# SCH_StringShotter_2025-03-04.net
KiCad netlist of a schematic drawn in EasyEDA
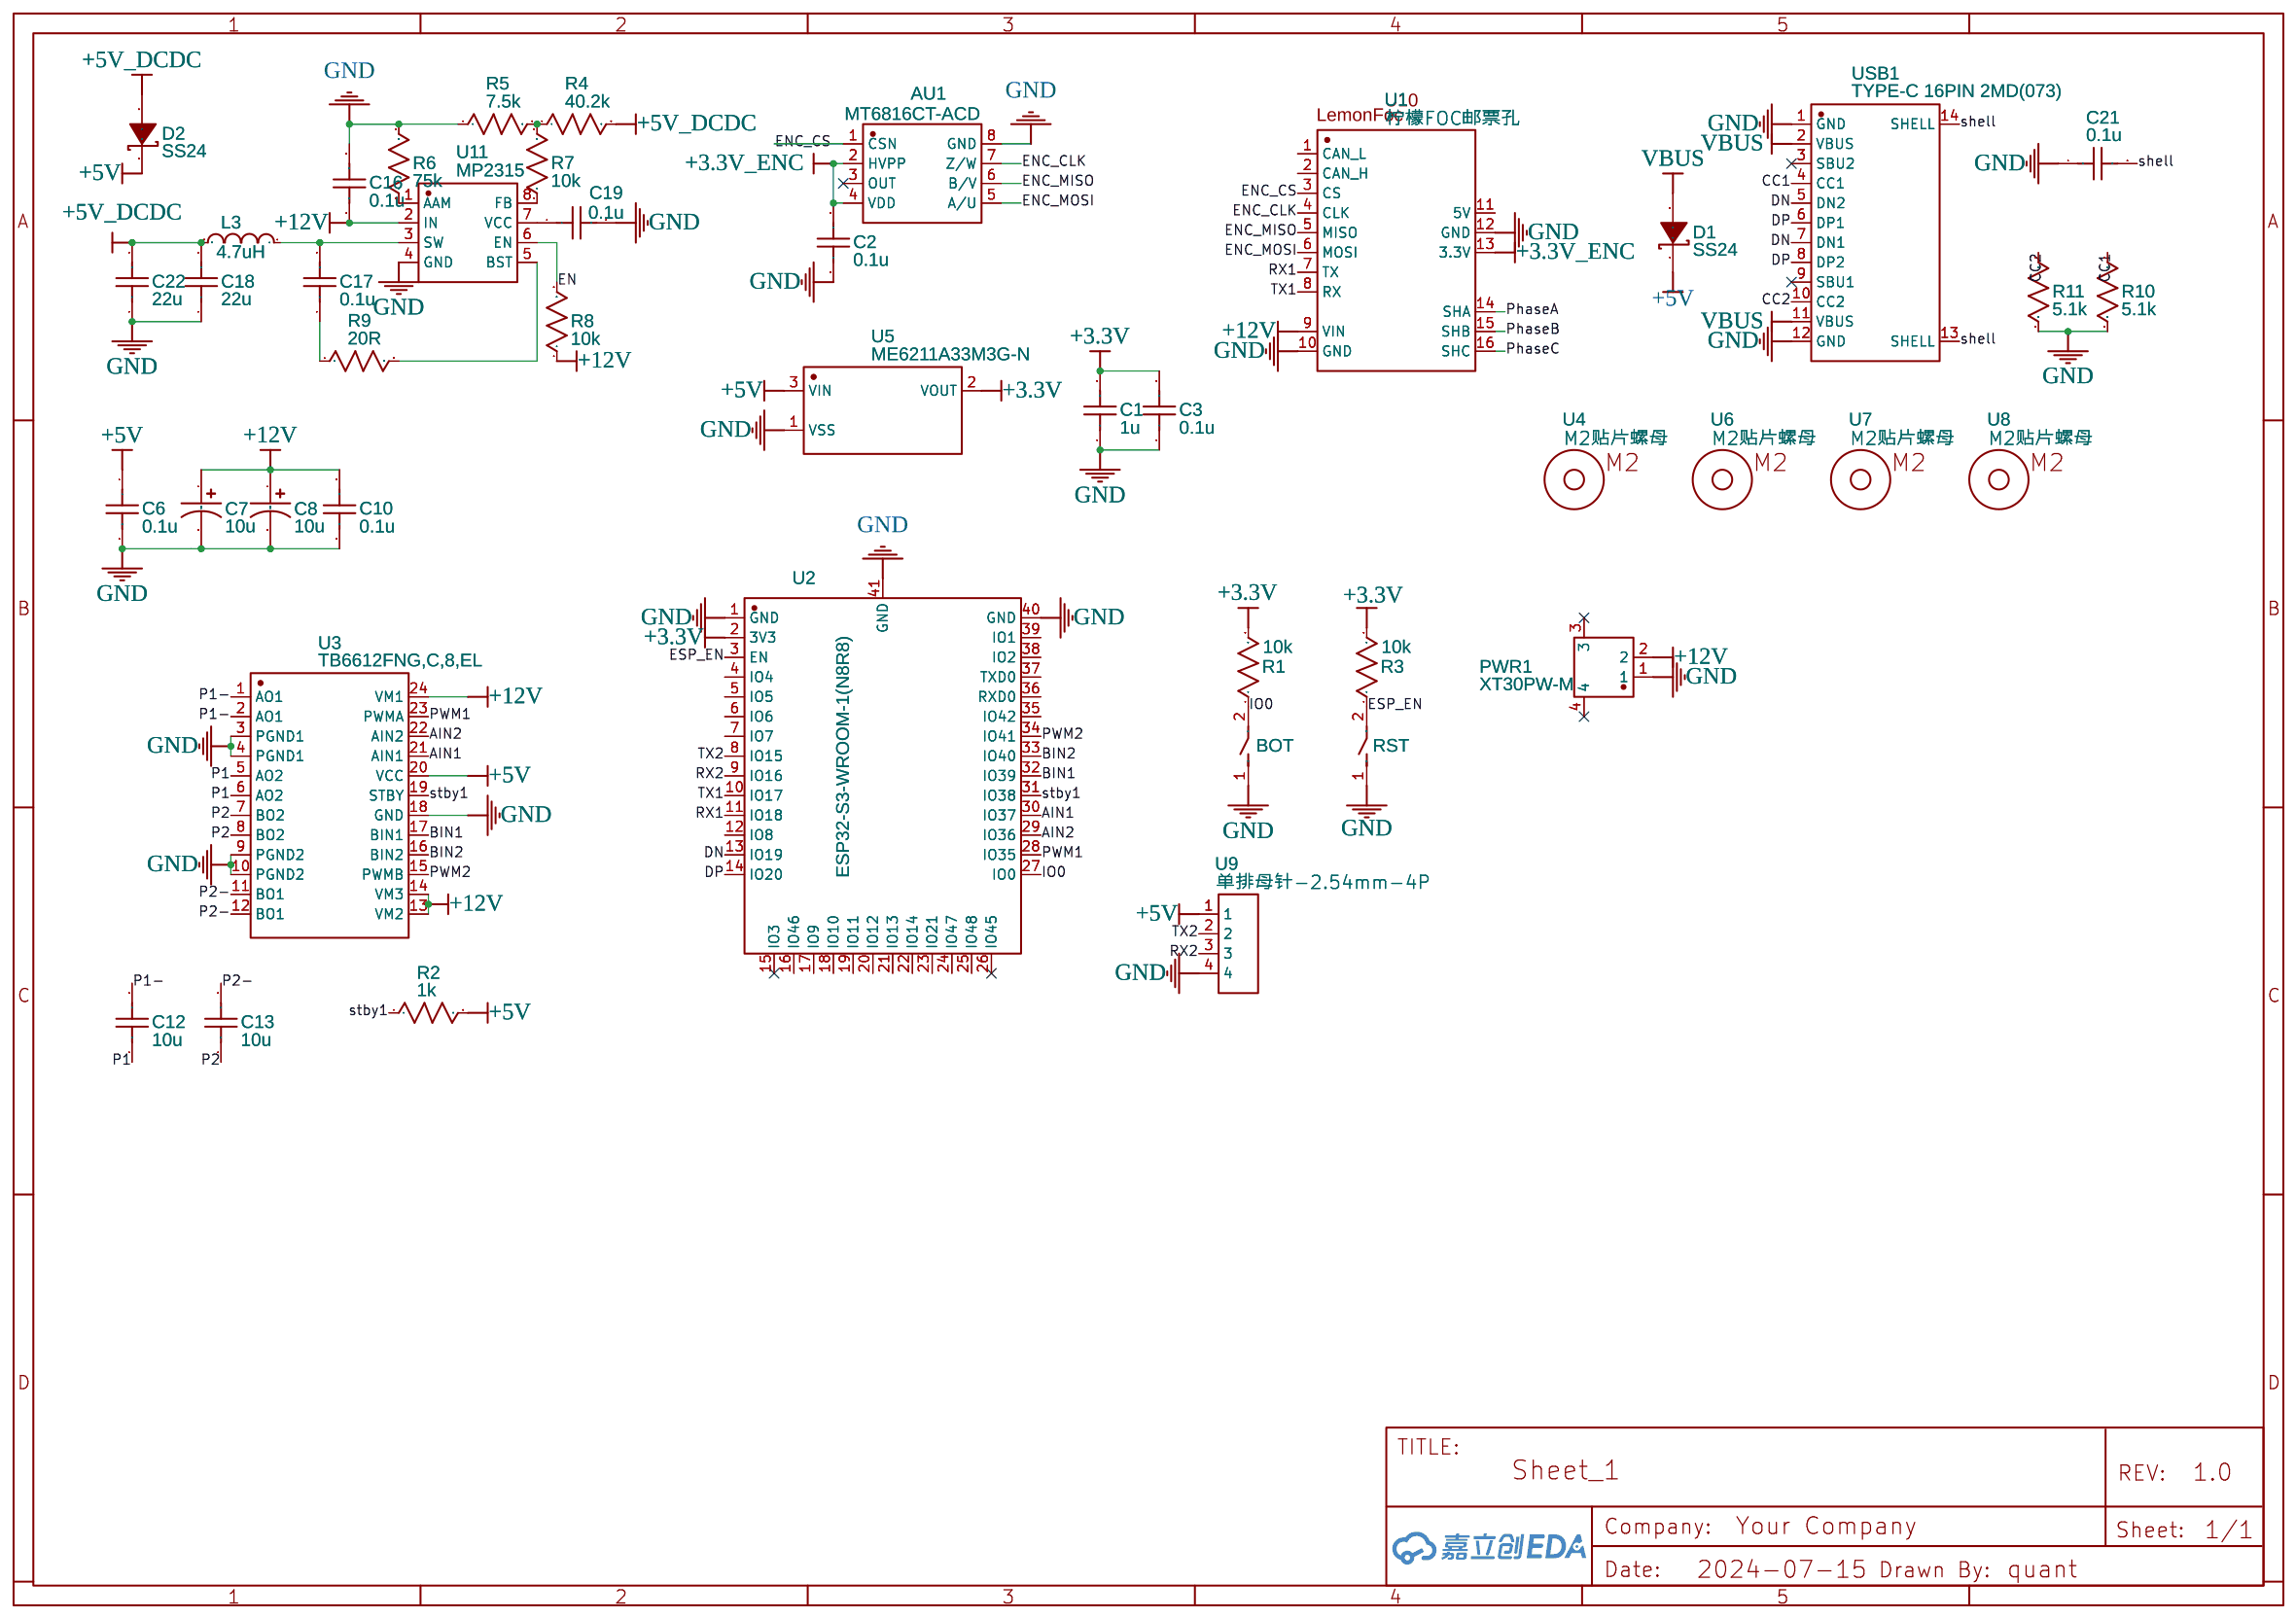
[diagram p0: schematic sheet]

(export (version "E")
  (design (tool "Eeschema 10.0.6"))
  (components
    (comp (ref "AU1")
      (value "MT6816CT-ACD")
      (fields (field (name "Manufacturer") "Magn Tek"))
      (libsource (lib "") (part "MT6816CT-ACD"))
    )
    (comp (ref "BOT")
      (value "TD-1106SN-5.0H-160")
      (fields (field (name "Manufacturer") "DEALON(德艺隆)"))
      (libsource (lib "") (part "TD-1106SN-5.0H-160_1"))
    )
    (comp (ref "C1") (value "1u") (libsource (lib "") (part "C_0603_US")))
    (comp (ref "C2") (value "0.1u") (libsource (lib "") (part "C_0603_US")))
    (comp (ref "C3") (value "0.1u") (libsource (lib "") (part "C_0603_US")))
    (comp (ref "C6") (value "0.1u") (libsource (lib "") (part "C_0603_US_1")))
    (comp (ref "C7") (value "10u") (libsource (lib "") (part "C_Tan_SMD_B_US")))
    (comp (ref "C8") (value "10u") (libsource (lib "") (part "C_Tan_SMD_B_US")))
    (comp (ref "C10") (value "0.1u") (libsource (lib "") (part "C_0603_US")))
    (comp (ref "C12") (value "10u") (libsource (lib "") (part "C_0805_US")))
    (comp (ref "C13") (value "10u") (libsource (lib "") (part "C_0805_US")))
    (comp (ref "C16") (value "0.1u") (libsource (lib "") (part "C_0603_US")))
    (comp (ref "C17") (value "0.1u") (libsource (lib "") (part "C_0603_US")))
    (comp (ref "C18") (value "22u") (libsource (lib "") (part "C_1206_US")))
    (comp (ref "C19") (value "0.1u") (libsource (lib "") (part "C_0603_US_2")))
    (comp (ref "C21") (value "0.1u") (libsource (lib "") (part "C_0603_US_2")))
    (comp (ref "C22") (value "22u") (libsource (lib "") (part "C_1206_US")))
    (comp (ref "D1")
      (value "SS24")
      (fields (field (name "Manufacturer") "MDD"))
      (libsource (lib "") (part "SS24"))
    )
    (comp (ref "D2")
      (value "SS24")
      (fields (field (name "Manufacturer") "MDD"))
      (libsource (lib "") (part "SS24"))
    )
    (comp (ref "L3")
      (value "4.7uH")
      (fields
        (field (name "Manufacturer Part") "MHCI06030-5R6M-R8")
        (field (name "Manufacturer") "Chilisin Elec")
      )
      (libsource (lib "") (part "MHCI06030-5R6M-R8"))
    )
    (comp (ref "PWR1")
      (value "XT30PW-M")
      (fields (field (name "Manufacturer") "Changzhou Amass Elec"))
      (libsource (lib "") (part "XT30PW-M"))
    )
    (comp (ref "R1") (value "10k") (libsource (lib "") (part "R_0603_US_1")))
    (comp (ref "R2") (value "1k") (libsource (lib "") (part "R_0603_US")))
    (comp (ref "R3") (value "10k") (libsource (lib "") (part "R_0603_US_1")))
    (comp (ref "R4") (value "40.2k") (libsource (lib "") (part "R_0603_US")))
    (comp (ref "R5") (value "7.5k") (libsource (lib "") (part "R_0603_US")))
    (comp (ref "R6") (value "75k") (libsource (lib "") (part "R_0603_US_1")))
    (comp (ref "R7") (value "10k") (libsource (lib "") (part "R_0603_US_1")))
    (comp (ref "R8") (value "10k") (libsource (lib "") (part "R_0603_US_1")))
    (comp (ref "R9") (value "20R") (libsource (lib "") (part "R_0603_US")))
    (comp (ref "R10") (value "5.1k") (libsource (lib "") (part "R_0603_US_2")))
    (comp (ref "R11") (value "5.1k") (libsource (lib "") (part "R_0603_US_2")))
    (comp (ref "RST")
      (value "TD-1106SN-5.0H-160")
      (fields (field (name "Manufacturer") "DEALON(德艺隆)"))
      (libsource (lib "") (part "TD-1106SN-5.0H-160"))
    )
    (comp (ref "U1") (value "柠檬FOC邮票孔") (libsource (lib "") (part "柠檬FOC邮票孔")))
    (comp (ref "U2")
      (value "ESP32-S3-WROOM-1(N8R8)")
      (fields (field (name "Manufacturer") "ESPRESSIF 乐鑫"))
      (libsource (lib "") (part "ESP32-S3-WROOM-1(N8R8)"))
    )
    (comp (ref "U3")
      (value "TB6612FNG,C,8,EL")
      (fields (field (name "Manufacturer") "TOSHIBA(东芝)"))
      (libsource (lib "") (part "TB6612FNG,C,8,EL"))
    )
    (comp (ref "U4") (value "M2贴片螺母") (libsource (lib "") (part "M2贴片螺母")))
    (comp (ref "U5")
      (value "ME6211A33M3G-N")
      (fields (field (name "Manufacturer") "MICRONE(南京微盟)"))
      (libsource (lib "") (part "ME6211A33M3G-N"))
    )
    (comp (ref "U6") (value "M2贴片螺母") (libsource (lib "") (part "M2贴片螺母")))
    (comp (ref "U7") (value "M2贴片螺母") (libsource (lib "") (part "M2贴片螺母")))
    (comp (ref "U8") (value "M2贴片螺母") (libsource (lib "") (part "M2贴片螺母")))
    (comp (ref "U9")
      (value "单排母针-2.54mm-4P")
      (fields (field (name "Manufacturer") "单排母针-2.54mm-6P"))
      (libsource (lib "") (part "单排母针-2.54mm-4P"))
    )
    (comp (ref "U11") (value "MP2315") (libsource (lib "") (part "MP2315")))
    (comp (ref "USB1")
      (value "TYPE-C 16PIN 2MD(073)")
      (fields (field (name "Manufacturer") "SHOU HAN(首韩)"))
      (libsource (lib "") (part "TYPE-C 16PIN 2MD(073)"))
    )
  )
  (nets
    (net (code "1") (name "+3.3V") (class "Default")
      (node (ref "C1") (pin "2") (pinfunction "2_2") (pintype "unspecified"))
      (node (ref "C3") (pin "2") (pinfunction "2_2") (pintype "unspecified"))
      (node (ref "R1") (pin "2") (pinfunction "2_2") (pintype "unspecified"))
      (node (ref "R3") (pin "2") (pinfunction "2_2") (pintype "unspecified"))
      (node (ref "U2") (pin "2") (pinfunction "3V3_2") (pintype "unspecified"))
      (node (ref "U5") (pin "2") (pinfunction "VOUT_2") (pintype "unspecified"))
    )
    (net (code "2") (name "+3.3V_ENC") (class "Default")
      (node (ref "AU1") (pin "2") (pinfunction "HVPP_2") (pintype "unspecified"))
      (node (ref "AU1") (pin "4") (pinfunction "VDD_4") (pintype "unspecified"))
      (node (ref "C2") (pin "2") (pinfunction "2_2") (pintype "unspecified"))
      (node (ref "U1") (pin "13") (pinfunction "3.3V_13") (pintype "unspecified"))
    )
    (net (code "3") (name "+5V") (class "Default")
      (node (ref "C6") (pin "1") (pinfunction "1_1") (pintype "unspecified"))
      (node (ref "D1") (pin "1") (pinfunction "K_1") (pintype "unspecified"))
      (node (ref "D2") (pin "1") (pinfunction "K_1") (pintype "unspecified"))
      (node (ref "R2") (pin "2") (pinfunction "2_2") (pintype "unspecified"))
      (node (ref "U3") (pin "20") (pinfunction "VCC_20") (pintype "unspecified"))
      (node (ref "U5") (pin "3") (pinfunction "VIN_3") (pintype "unspecified"))
      (node (ref "U9") (pin "1") (pinfunction "1_1") (pintype "unspecified"))
    )
    (net (code "4") (name "+5V_DCDC") (class "Default")
      (node (ref "C18") (pin "2") (pinfunction "2_2") (pintype "unspecified"))
      (node (ref "C22") (pin "2") (pinfunction "2_2") (pintype "unspecified"))
      (node (ref "D2") (pin "2") (pinfunction "A_2") (pintype "unspecified"))
      (node (ref "L3") (pin "2") (pinfunction "2_2") (pintype "unspecified"))
      (node (ref "R4") (pin "2") (pinfunction "2_2") (pintype "unspecified"))
    )
    (net (code "5") (name "+12V") (class "Default")
      (node (ref "C10") (pin "2") (pinfunction "2_2") (pintype "unspecified"))
      (node (ref "C16") (pin "1") (pinfunction "1_1") (pintype "unspecified"))
      (node (ref "C7") (pin "1") (pinfunction "1_1") (pintype "unspecified"))
      (node (ref "C8") (pin "1") (pinfunction "1_1") (pintype "unspecified"))
      (node (ref "PWR1") (pin "2") (pinfunction "2_2") (pintype "unspecified"))
      (node (ref "R8") (pin "1") (pinfunction "1_1") (pintype "unspecified"))
      (node (ref "U1") (pin "9") (pinfunction "VIN_9") (pintype "unspecified"))
      (node (ref "U11") (pin "2") (pinfunction "IN_2") (pintype "unspecified"))
      (node (ref "U3") (pin "13") (pinfunction "VM2_13") (pintype "unspecified"))
      (node (ref "U3") (pin "14") (pinfunction "VM3_14") (pintype "unspecified"))
      (node (ref "U3") (pin "24") (pinfunction "VM1_24") (pintype "unspecified"))
    )
    (net (code "6") (name "/AIN1") (class "Default")
      (node (ref "U2") (pin "30") (pinfunction "IO37_30") (pintype "unspecified"))
      (node (ref "U3") (pin "21") (pinfunction "AIN1_21") (pintype "unspecified"))
    )
    (net (code "7") (name "/AIN2") (class "Default")
      (node (ref "U2") (pin "29") (pinfunction "IO36_29") (pintype "unspecified"))
      (node (ref "U3") (pin "22") (pinfunction "AIN2_22") (pintype "unspecified"))
    )
    (net (code "8") (name "/BIN1") (class "Default")
      (node (ref "U2") (pin "32") (pinfunction "IO39_32") (pintype "unspecified"))
      (node (ref "U3") (pin "17") (pinfunction "BIN1_17") (pintype "unspecified"))
    )
    (net (code "9") (name "/BIN2") (class "Default")
      (node (ref "U2") (pin "33") (pinfunction "IO40_33") (pintype "unspecified"))
      (node (ref "U3") (pin "16") (pinfunction "BIN2_16") (pintype "unspecified"))
    )
    (net (code "10") (name "/CC1") (class "Default")
      (node (ref "R10") (pin "1") (pinfunction "1_1") (pintype "unspecified"))
      (node (ref "USB1") (pin "4") (pinfunction "CC1_4") (pintype "unspecified"))
    )
    (net (code "11") (name "/CC2") (class "Default")
      (node (ref "R11") (pin "1") (pinfunction "1_1") (pintype "unspecified"))
      (node (ref "USB1") (pin "10") (pinfunction "CC2_10") (pintype "unspecified"))
    )
    (net (code "12") (name "/DN") (class "Default")
      (node (ref "U2") (pin "13") (pinfunction "IO19_13") (pintype "unspecified"))
      (node (ref "USB1") (pin "5") (pinfunction "DN2_5") (pintype "unspecified"))
      (node (ref "USB1") (pin "7") (pinfunction "DN1_7") (pintype "unspecified"))
    )
    (net (code "13") (name "/DP") (class "Default")
      (node (ref "U2") (pin "14") (pinfunction "IO20_14") (pintype "unspecified"))
      (node (ref "USB1") (pin "6") (pinfunction "DP1_6") (pintype "unspecified"))
      (node (ref "USB1") (pin "8") (pinfunction "DP2_8") (pintype "unspecified"))
    )
    (net (code "14") (name "/EN") (class "Default")
      (node (ref "R8") (pin "2") (pinfunction "2_2") (pintype "unspecified"))
      (node (ref "U11") (pin "6") (pinfunction "EN_6") (pintype "unspecified"))
    )
    (net (code "15") (name "/ENC_CLK") (class "Default")
      (node (ref "AU1") (pin "7") (pinfunction "Z/W_7") (pintype "unspecified"))
      (node (ref "U1") (pin "4") (pinfunction "CLK_4") (pintype "unspecified"))
    )
    (net (code "16") (name "/ENC_CS") (class "Default")
      (node (ref "AU1") (pin "1") (pinfunction "CSN_1") (pintype "unspecified"))
      (node (ref "U1") (pin "3") (pinfunction "CS_3") (pintype "unspecified"))
    )
    (net (code "17") (name "/ENC_MISO") (class "Default")
      (node (ref "AU1") (pin "6") (pinfunction "B/V_6") (pintype "unspecified"))
      (node (ref "U1") (pin "5") (pinfunction "MISO_5") (pintype "unspecified"))
    )
    (net (code "18") (name "/ENC_MOSI") (class "Default")
      (node (ref "AU1") (pin "5") (pinfunction "A/U_5") (pintype "unspecified"))
      (node (ref "U1") (pin "6") (pinfunction "MOSI_6") (pintype "unspecified"))
    )
    (net (code "19") (name "/ESP_EN") (class "Default")
      (node (ref "R3") (pin "1") (pinfunction "1_1") (pintype "unspecified"))
      (node (ref "RST") (pin "2") (pinfunction "2_2") (pintype "unspecified"))
      (node (ref "U2") (pin "3") (pinfunction "EN_3") (pintype "unspecified"))
    )
    (net (code "20") (name "/IO0") (class "Default")
      (node (ref "BOT") (pin "2") (pinfunction "2_2") (pintype "unspecified"))
      (node (ref "R1") (pin "1") (pinfunction "1_1") (pintype "unspecified"))
      (node (ref "U2") (pin "27") (pinfunction "IO0_27") (pintype "unspecified"))
    )
    (net (code "21") (name "/P1") (class "Default")
      (node (ref "C12") (pin "1") (pinfunction "1_1") (pintype "unspecified"))
      (node (ref "U3") (pin "5") (pinfunction "AO2_5") (pintype "unspecified"))
      (node (ref "U3") (pin "6") (pinfunction "AO2_6") (pintype "unspecified"))
    )
    (net (code "22") (name "/P1-") (class "Default")
      (node (ref "C12") (pin "2") (pinfunction "2_2") (pintype "unspecified"))
      (node (ref "U3") (pin "1") (pinfunction "AO1_1") (pintype "unspecified"))
      (node (ref "U3") (pin "2") (pinfunction "AO1_2") (pintype "unspecified"))
    )
    (net (code "23") (name "/P2") (class "Default")
      (node (ref "C13") (pin "1") (pinfunction "1_1") (pintype "unspecified"))
      (node (ref "U3") (pin "7") (pinfunction "BO2_7") (pintype "unspecified"))
      (node (ref "U3") (pin "8") (pinfunction "BO2_8") (pintype "unspecified"))
    )
    (net (code "24") (name "/P2-") (class "Default")
      (node (ref "C13") (pin "2") (pinfunction "2_2") (pintype "unspecified"))
      (node (ref "U3") (pin "11") (pinfunction "BO1_11") (pintype "unspecified"))
      (node (ref "U3") (pin "12") (pinfunction "BO1_12") (pintype "unspecified"))
    )
    (net (code "25") (name "/PWM1") (class "Default")
      (node (ref "U2") (pin "28") (pinfunction "IO35_28") (pintype "unspecified"))
      (node (ref "U3") (pin "23") (pinfunction "PWMA_23") (pintype "unspecified"))
    )
    (net (code "26") (name "/PWM2") (class "Default")
      (node (ref "U2") (pin "34") (pinfunction "IO41_34") (pintype "unspecified"))
      (node (ref "U3") (pin "15") (pinfunction "PWMB_15") (pintype "unspecified"))
    )
    (net (code "27") (name "/PhaseA") (class "Default")
      (node (ref "U1") (pin "14") (pinfunction "SHA_14") (pintype "unspecified"))
    )
    (net (code "28") (name "/PhaseB") (class "Default")
      (node (ref "U1") (pin "15") (pinfunction "SHB_15") (pintype "unspecified"))
    )
    (net (code "29") (name "/PhaseC") (class "Default")
      (node (ref "U1") (pin "16") (pinfunction "SHC_16") (pintype "unspecified"))
    )
    (net (code "30") (name "/RX1") (class "Default")
      (node (ref "U1") (pin "7") (pinfunction "TX_7") (pintype "unspecified"))
      (node (ref "U2") (pin "11") (pinfunction "IO18_11") (pintype "unspecified"))
    )
    (net (code "31") (name "/RX2") (class "Default")
      (node (ref "U2") (pin "9") (pinfunction "IO16_9") (pintype "unspecified"))
      (node (ref "U9") (pin "3") (pinfunction "3_3") (pintype "unspecified"))
    )
    (net (code "32") (name "/TX1") (class "Default")
      (node (ref "U1") (pin "8") (pinfunction "RX_8") (pintype "unspecified"))
      (node (ref "U2") (pin "10") (pinfunction "IO17_10") (pintype "unspecified"))
    )
    (net (code "33") (name "/TX2") (class "Default")
      (node (ref "U2") (pin "8") (pinfunction "IO15_8") (pintype "unspecified"))
      (node (ref "U9") (pin "2") (pinfunction "2_2") (pintype "unspecified"))
    )
    (net (code "34") (name "/shell") (class "Default")
      (node (ref "C21") (pin "2") (pinfunction "2_2") (pintype "unspecified"))
      (node (ref "USB1") (pin "13") (pinfunction "SHELL_13") (pintype "unspecified"))
      (node (ref "USB1") (pin "14") (pinfunction "SHELL_14") (pintype "unspecified"))
    )
    (net (code "35") (name "/stby1") (class "Default")
      (node (ref "R2") (pin "1") (pinfunction "1_1") (pintype "unspecified"))
      (node (ref "U2") (pin "31") (pinfunction "IO38_31") (pintype "unspecified"))
      (node (ref "U3") (pin "19") (pinfunction "STBY_19") (pintype "unspecified"))
    )
    (net (code "36") (name "GND") (class "Default")
      (node (ref "AU1") (pin "8") (pinfunction "GND_8") (pintype "unspecified"))
      (node (ref "BOT") (pin "1") (pinfunction "1_1") (pintype "unspecified"))
      (node (ref "C1") (pin "1") (pinfunction "1_1") (pintype "unspecified"))
      (node (ref "C10") (pin "1") (pinfunction "1_1") (pintype "unspecified"))
      (node (ref "C16") (pin "2") (pinfunction "2_2") (pintype "unspecified"))
      (node (ref "C18") (pin "1") (pinfunction "1_1") (pintype "unspecified"))
      (node (ref "C19") (pin "2") (pinfunction "2_2") (pintype "unspecified"))
      (node (ref "C2") (pin "1") (pinfunction "1_1") (pintype "unspecified"))
      (node (ref "C21") (pin "1") (pinfunction "1_1") (pintype "unspecified"))
      (node (ref "C22") (pin "1") (pinfunction "1_1") (pintype "unspecified"))
      (node (ref "C3") (pin "1") (pinfunction "1_1") (pintype "unspecified"))
      (node (ref "C6") (pin "2") (pinfunction "2_2") (pintype "unspecified"))
      (node (ref "C7") (pin "2") (pinfunction "2_2") (pintype "unspecified"))
      (node (ref "C8") (pin "2") (pinfunction "2_2") (pintype "unspecified"))
      (node (ref "PWR1") (pin "1") (pinfunction "1_1") (pintype "unspecified"))
      (node (ref "R10") (pin "2") (pinfunction "2_2") (pintype "unspecified"))
      (node (ref "R11") (pin "2") (pinfunction "2_2") (pintype "unspecified"))
      (node (ref "R5") (pin "1") (pinfunction "1_1") (pintype "unspecified"))
      (node (ref "R6") (pin "2") (pinfunction "2_2") (pintype "unspecified"))
      (node (ref "RST") (pin "1") (pinfunction "1_1") (pintype "unspecified"))
      (node (ref "U1") (pin "10") (pinfunction "GND_10") (pintype "unspecified"))
      (node (ref "U1") (pin "12") (pinfunction "GND_12") (pintype "unspecified"))
      (node (ref "U11") (pin "4") (pinfunction "GND_4") (pintype "unspecified"))
      (node (ref "U2") (pin "1") (pinfunction "GND_1") (pintype "unspecified"))
      (node (ref "U2") (pin "40") (pinfunction "GND_40") (pintype "unspecified"))
      (node (ref "U2") (pin "41") (pinfunction "GND_41") (pintype "unspecified"))
      (node (ref "U3") (pin "10") (pinfunction "PGND2_10") (pintype "unspecified"))
      (node (ref "U3") (pin "18") (pinfunction "GND_18") (pintype "unspecified"))
      (node (ref "U3") (pin "3") (pinfunction "PGND1_3") (pintype "unspecified"))
      (node (ref "U3") (pin "4") (pinfunction "PGND1_4") (pintype "unspecified"))
      (node (ref "U3") (pin "9") (pinfunction "PGND2_9") (pintype "unspecified"))
      (node (ref "U5") (pin "1") (pinfunction "VSS_1") (pintype "unspecified"))
      (node (ref "U9") (pin "4") (pinfunction "4_4") (pintype "unspecified"))
      (node (ref "USB1") (pin "1") (pinfunction "GND_1") (pintype "unspecified"))
      (node (ref "USB1") (pin "12") (pinfunction "GND_12") (pintype "unspecified"))
    )
    (net (code "37") (name "Net-(C17-Pad1)") (class "Default")
      (node (ref "C17") (pin "1") (pinfunction "1_1") (pintype "unspecified"))
      (node (ref "R9") (pin "1") (pinfunction "1_1") (pintype "unspecified"))
    )
    (net (code "38") (name "Net-(R4-Pad1)") (class "Default")
      (node (ref "R4") (pin "1") (pinfunction "1_1") (pintype "unspecified"))
      (node (ref "R5") (pin "2") (pinfunction "2_2") (pintype "unspecified"))
      (node (ref "R7") (pin "2") (pinfunction "2_2") (pintype "unspecified"))
    )
    (net (code "39") (name "Net-(U11-AAM)") (class "Default")
      (node (ref "R6") (pin "1") (pinfunction "1_1") (pintype "unspecified"))
      (node (ref "U11") (pin "1") (pinfunction "AAM_1") (pintype "unspecified"))
    )
    (net (code "40") (name "Net-(U11-BST)") (class "Default")
      (node (ref "R9") (pin "2") (pinfunction "2_2") (pintype "unspecified"))
      (node (ref "U11") (pin "5") (pinfunction "BST_5") (pintype "unspecified"))
    )
    (net (code "41") (name "Net-(U11-FB)") (class "Default")
      (node (ref "R7") (pin "1") (pinfunction "1_1") (pintype "unspecified"))
      (node (ref "U11") (pin "8") (pinfunction "FB_8") (pintype "unspecified"))
    )
    (net (code "42") (name "Net-(U11-SW)") (class "Default")
      (node (ref "C17") (pin "2") (pinfunction "2_2") (pintype "unspecified"))
      (node (ref "L3") (pin "1") (pinfunction "1_1") (pintype "unspecified"))
      (node (ref "U11") (pin "3") (pinfunction "SW_3") (pintype "unspecified"))
    )
    (net (code "43") (name "Net-(U11-VCC)") (class "Default")
      (node (ref "C19") (pin "1") (pinfunction "1_1") (pintype "unspecified"))
      (node (ref "U11") (pin "7") (pinfunction "VCC_7") (pintype "unspecified"))
    )
    (net (code "44") (name "VBUS") (class "Default")
      (node (ref "D1") (pin "2") (pinfunction "A_2") (pintype "unspecified"))
      (node (ref "USB1") (pin "11") (pinfunction "VBUS_11") (pintype "unspecified"))
      (node (ref "USB1") (pin "2") (pinfunction "VBUS_2") (pintype "unspecified"))
    )
    (net (code "45") (name "unconnected-(AU1-OUT-Pad3)") (class "Default")
      (node (ref "AU1") (pin "3") (pinfunction "OUT_3") (pintype "unspecified+no_connect"))
    )
    (net (code "46") (name "unconnected-(PWR1-Pad3)") (class "Default")
      (node (ref "PWR1") (pin "3") (pinfunction "3_3") (pintype "unspecified+no_connect"))
    )
    (net (code "47") (name "unconnected-(PWR1-Pad4)") (class "Default")
      (node (ref "PWR1") (pin "4") (pinfunction "4_4") (pintype "unspecified+no_connect"))
    )
    (net (code "48") (name "unconnected-(U1-5V-Pad11)") (class "Default")
      (node (ref "U1") (pin "11") (pinfunction "5V_11") (pintype "unspecified"))
    )
    (net (code "49") (name "unconnected-(U1-CAN_H-Pad2)") (class "Default")
      (node (ref "U1") (pin "2") (pinfunction "CAN_H_2") (pintype "unspecified"))
    )
    (net (code "50") (name "unconnected-(U1-CAN_L-Pad1)") (class "Default")
      (node (ref "U1") (pin "1") (pinfunction "CAN_L_1") (pintype "unspecified"))
    )
    (net (code "51") (name "unconnected-(U2-IO1-Pad39)") (class "Default")
      (node (ref "U2") (pin "39") (pinfunction "IO1_39") (pintype "unspecified"))
    )
    (net (code "52") (name "unconnected-(U2-IO2-Pad38)") (class "Default")
      (node (ref "U2") (pin "38") (pinfunction "IO2_38") (pintype "unspecified"))
    )
    (net (code "53") (name "unconnected-(U2-IO3-Pad15)") (class "Default")
      (node (ref "U2") (pin "15") (pinfunction "IO3_15") (pintype "unspecified+no_connect"))
    )
    (net (code "54") (name "unconnected-(U2-IO4-Pad4)") (class "Default")
      (node (ref "U2") (pin "4") (pinfunction "IO4_4") (pintype "unspecified"))
    )
    (net (code "55") (name "unconnected-(U2-IO5-Pad5)") (class "Default")
      (node (ref "U2") (pin "5") (pinfunction "IO5_5") (pintype "unspecified"))
    )
    (net (code "56") (name "unconnected-(U2-IO6-Pad6)") (class "Default")
      (node (ref "U2") (pin "6") (pinfunction "IO6_6") (pintype "unspecified"))
    )
    (net (code "57") (name "unconnected-(U2-IO7-Pad7)") (class "Default")
      (node (ref "U2") (pin "7") (pinfunction "IO7_7") (pintype "unspecified"))
    )
    (net (code "58") (name "unconnected-(U2-IO8-Pad12)") (class "Default")
      (node (ref "U2") (pin "12") (pinfunction "IO8_12") (pintype "unspecified"))
    )
    (net (code "59") (name "unconnected-(U2-IO9-Pad17)") (class "Default")
      (node (ref "U2") (pin "17") (pinfunction "IO9_17") (pintype "unspecified"))
    )
    (net (code "60") (name "unconnected-(U2-IO10-Pad18)") (class "Default")
      (node (ref "U2") (pin "18") (pinfunction "IO10_18") (pintype "unspecified"))
    )
    (net (code "61") (name "unconnected-(U2-IO11-Pad19)") (class "Default")
      (node (ref "U2") (pin "19") (pinfunction "IO11_19") (pintype "unspecified"))
    )
    (net (code "62") (name "unconnected-(U2-IO12-Pad20)") (class "Default")
      (node (ref "U2") (pin "20") (pinfunction "IO12_20") (pintype "unspecified"))
    )
    (net (code "63") (name "unconnected-(U2-IO13-Pad21)") (class "Default")
      (node (ref "U2") (pin "21") (pinfunction "IO13_21") (pintype "unspecified"))
    )
    (net (code "64") (name "unconnected-(U2-IO14-Pad22)") (class "Default")
      (node (ref "U2") (pin "22") (pinfunction "IO14_22") (pintype "unspecified"))
    )
    (net (code "65") (name "unconnected-(U2-IO21-Pad23)") (class "Default")
      (node (ref "U2") (pin "23") (pinfunction "IO21_23") (pintype "unspecified"))
    )
    (net (code "66") (name "unconnected-(U2-IO42-Pad35)") (class "Default")
      (node (ref "U2") (pin "35") (pinfunction "IO42_35") (pintype "unspecified"))
    )
    (net (code "67") (name "unconnected-(U2-IO45-Pad26)") (class "Default")
      (node (ref "U2") (pin "26") (pinfunction "IO45_26") (pintype "unspecified+no_connect"))
    )
    (net (code "68") (name "unconnected-(U2-IO46-Pad16)") (class "Default")
      (node (ref "U2") (pin "16") (pinfunction "IO46_16") (pintype "unspecified"))
    )
    (net (code "69") (name "unconnected-(U2-IO47-Pad24)") (class "Default")
      (node (ref "U2") (pin "24") (pinfunction "IO47_24") (pintype "unspecified"))
    )
    (net (code "70") (name "unconnected-(U2-IO48-Pad25)") (class "Default")
      (node (ref "U2") (pin "25") (pinfunction "IO48_25") (pintype "unspecified"))
    )
    (net (code "71") (name "unconnected-(U2-RXD0-Pad36)") (class "Default")
      (node (ref "U2") (pin "36") (pinfunction "RXD0_36") (pintype "unspecified"))
    )
    (net (code "72") (name "unconnected-(U2-TXD0-Pad37)") (class "Default")
      (node (ref "U2") (pin "37") (pinfunction "TXD0_37") (pintype "unspecified"))
    )
    (net (code "73") (name "unconnected-(USB1-SBU1-Pad9)") (class "Default")
      (node (ref "USB1") (pin "9") (pinfunction "SBU1_9") (pintype "unspecified+no_connect"))
    )
    (net (code "74") (name "unconnected-(USB1-SBU2-Pad3)") (class "Default")
      (node (ref "USB1") (pin "3") (pinfunction "SBU2_3") (pintype "unspecified+no_connect"))
    )
  )
)
